# HuLaMachDieuKhienSCH.net
KiCad netlist of a schematic drawn in Altium Designer
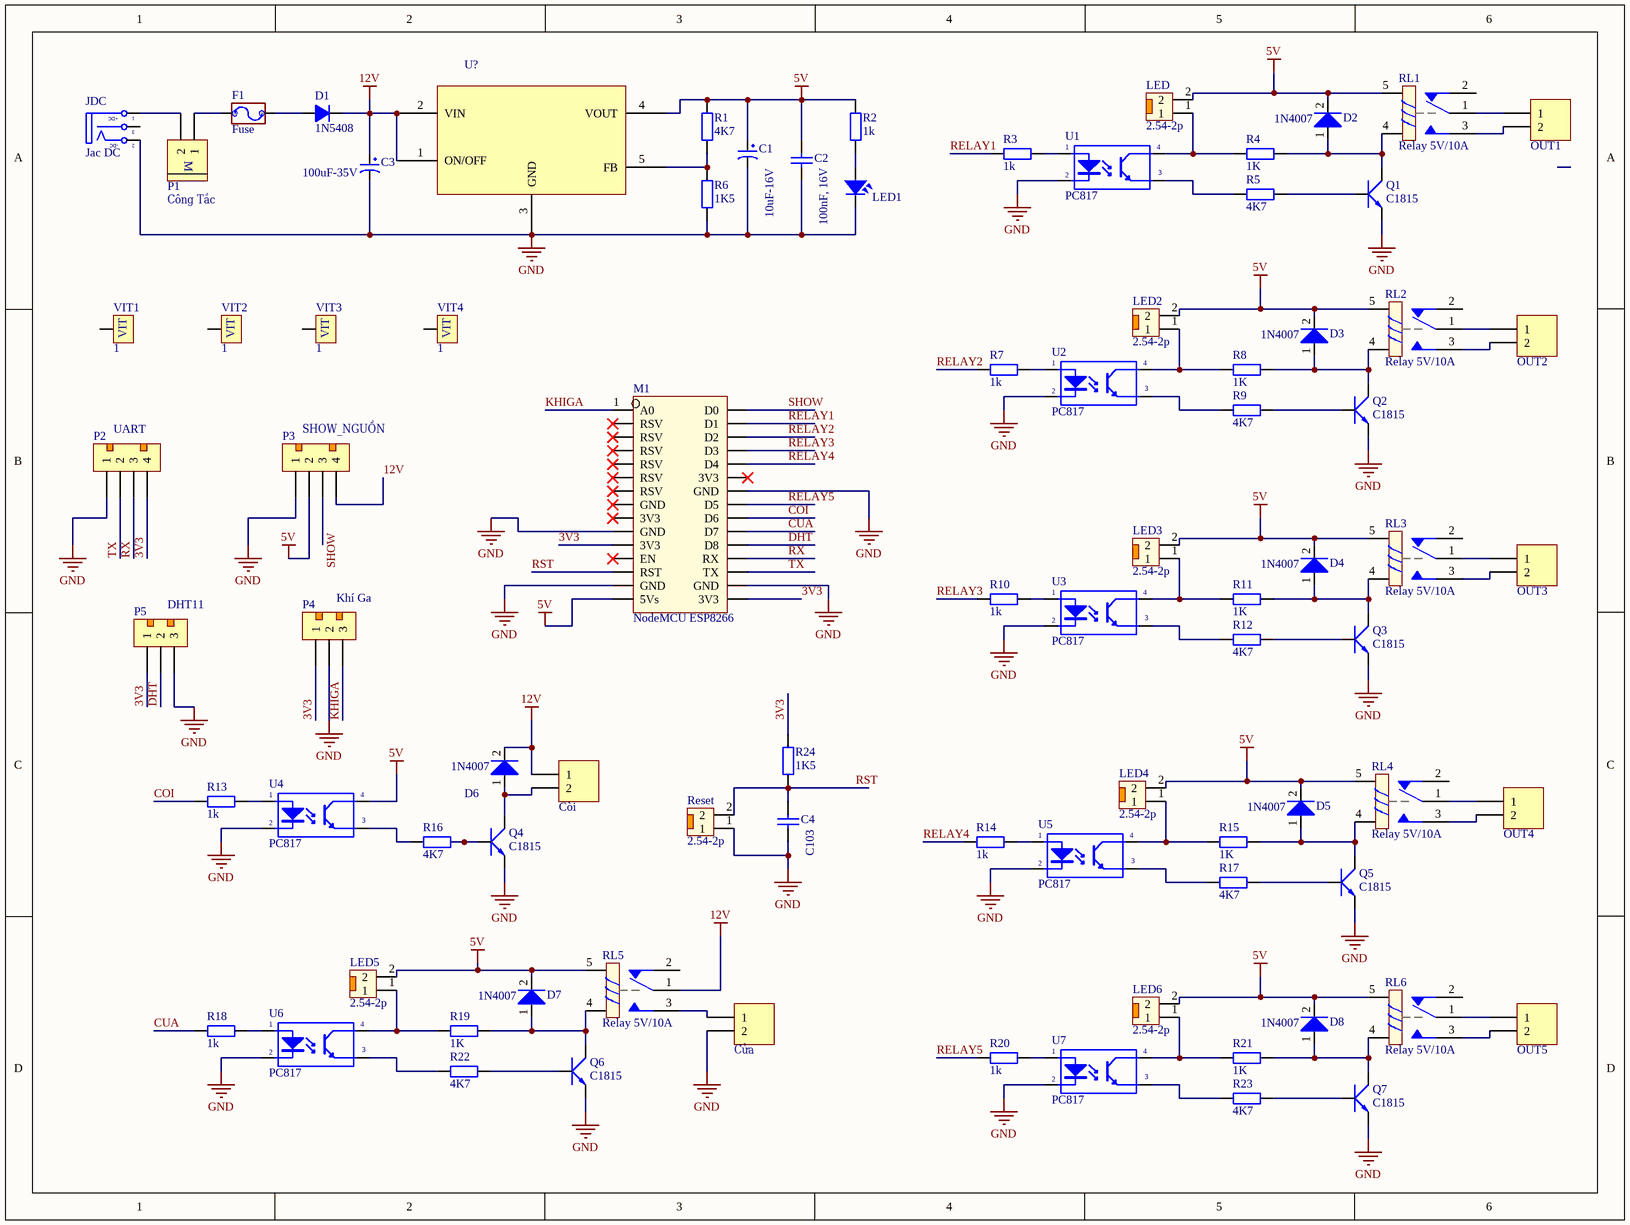
[diagram p0: HuLaMachDieuKhienSCH.SchDoc]

(export (version "E")
  (design (tool "Eeschema 10.0.6"))
  (components
    (comp (ref "C1")
      (value "10uF-16V")
      (footprint "tu hoa 4mm")
      (description "Cắm")
      (libsource (lib "SCH Chuan") (part "Tu Hoa 10uF 16V 4x7"))
    )
    (comp (ref "C2")
      (value "100nF, 16V")
      (footprint "CAPNTO2.54-3.05x1.78A")
      (description "CAP NPO CAPNTO 22pF 100V 10%")
      (fields (field (name "Comment") "5AK220KABAA"))
      (libsource (lib "NhomLib") (part "5AK220KABAA"))
    )
    (comp (ref "C3")
      (value "100uF-35V")
      (footprint "tu hoa 6.5mm")
      (description "Cắm")
      (libsource (lib "SCH Chuan") (part "Tu Hoa 100uF 35V 6x8"))
    )
    (comp (ref "C4")
      (value "C103")
      (footprint "CAPNTO2.54-3.05x1.78A")
      (description "CAP NPO CAPNTO 22pF 100V 10%")
      (fields (field (name "Comment") "5AK220KABAA"))
      (libsource (lib "NhomLib") (part "5AK220KABAA"))
    )
    (comp (ref "Còi")
      (value "Header 2_1")
      (footprint "HED2")
      (description "Header, 2-Pin")
      (fields (field (name "MANUFACTURER") "Generic Components"))
      (libsource (lib "syhaunguyen") (part "Header 2_1"))
    )
    (comp (ref "Cửa")
      (value "Header 2_1")
      (footprint "HED2")
      (description "Header, 2-Pin")
      (fields (field (name "MANUFACTURER") "Generic Components"))
      (libsource (lib "syhaunguyen") (part "Header 2_1"))
    )
    (comp (ref "D1")
      (value "1N5408")
      (footprint "D5A")
      (description "Diode 5A")
      (libsource (lib "syhaunguyen") (part "D5A"))
    )
    (comp (ref "D2")
      (value "1N4007")
      (footprint "1N4007")
      (description "Diode LS 1A 1000V DO-41")
      (libsource (lib "LPSON") (part "1N4007"))
    )
    (comp (ref "D3")
      (value "1N4007")
      (footprint "1N4007")
      (description "Diode LS 1A 1000V DO-41")
      (libsource (lib "LPSON") (part "1N4007"))
    )
    (comp (ref "D4")
      (value "1N4007")
      (footprint "1N4007")
      (description "Diode LS 1A 1000V DO-41")
      (libsource (lib "LPSON") (part "1N4007"))
    )
    (comp (ref "D5")
      (value "1N4007")
      (footprint "1N4007")
      (description "Diode LS 1A 1000V DO-41")
      (libsource (lib "LPSON") (part "1N4007"))
    )
    (comp (ref "D6")
      (value "1N4007")
      (footprint "1N4007")
      (description "Diode LS 1A 1000V DO-41")
      (libsource (lib "LPSON") (part "1N4007"))
    )
    (comp (ref "D7")
      (value "1N4007")
      (footprint "1N4007")
      (description "Diode LS 1A 1000V DO-41")
      (libsource (lib "LPSON") (part "1N4007"))
    )
    (comp (ref "D8")
      (value "1N4007")
      (footprint "1N4007")
      (description "Diode LS 1A 1000V DO-41")
      (libsource (lib "LPSON") (part "1N4007"))
    )
    (comp (ref "F1") (value "Fuse") (footprint "FUSE_BOX") (libsource (lib "VPMyLibrary") (part "Fuse")))
    (comp (ref "JDC")
      (value "Jac DC")
      (footprint "DC-IN")
      (description "Jac DC input")
      (libsource (lib "LPSON") (part "DCIN"))
    )
    (comp (ref "LED")
      (value "2.54-2p")
      (footprint "Header Duc Thang 2P 2.54")
      (description "Cắm")
      (libsource (lib "NhomLib") (part "Header 2.54-2p Duc Thang"))
    )
    (comp (ref "LED1")
      (value "LED")
      (footprint "LED-3")
      (description "LED Single colour Green and Red")
      (libsource (lib "syhaunguyen") (part "LED"))
    )
    (comp (ref "LED2")
      (value "2.54-2p")
      (footprint "Header Duc Thang 2P 2.54")
      (description "Cắm")
      (libsource (lib "NhomLib") (part "Header 2.54-2p Duc Thang"))
    )
    (comp (ref "LED3")
      (value "2.54-2p")
      (footprint "Header Duc Thang 2P 2.54")
      (description "Cắm")
      (libsource (lib "NhomLib") (part "Header 2.54-2p Duc Thang"))
    )
    (comp (ref "LED4")
      (value "2.54-2p")
      (footprint "Header Duc Thang 2P 2.54")
      (description "Cắm")
      (libsource (lib "NhomLib") (part "Header 2.54-2p Duc Thang"))
    )
    (comp (ref "LED5")
      (value "2.54-2p")
      (footprint "Header Duc Thang 2P 2.54")
      (description "Cắm")
      (libsource (lib "NhomLib") (part "Header 2.54-2p Duc Thang"))
    )
    (comp (ref "LED6")
      (value "2.54-2p")
      (footprint "Header Duc Thang 2P 2.54")
      (description "Cắm")
      (libsource (lib "NhomLib") (part "Header 2.54-2p Duc Thang"))
    )
    (comp (ref "M1")
      (value "NodeMCU ESP8266")
      (footprint "NodeMCU ESP8266")
      (libsource (lib "NodeMCU ESP8266") (part "NodeMCU ESP8266"))
    )
    (comp (ref "MIC1")
      (value "U?")
      (footprint "Mic5V")
      (description "3A")
      (libsource (lib "node_mcu") (part "Mic5V"))
    )
    (comp (ref "OUT1")
      (value "Header 2_1")
      (footprint "HED2")
      (description "Header, 2-Pin")
      (fields (field (name "MANUFACTURER") "Generic Components"))
      (libsource (lib "syhaunguyen") (part "Header 2_1"))
    )
    (comp (ref "OUT2")
      (value "Header 2_1")
      (footprint "HED2")
      (description "Header, 2-Pin")
      (fields (field (name "MANUFACTURER") "Generic Components"))
      (libsource (lib "syhaunguyen") (part "Header 2_1"))
    )
    (comp (ref "OUT3")
      (value "Header 2_1")
      (footprint "HED2")
      (description "Header, 2-Pin")
      (fields (field (name "MANUFACTURER") "Generic Components"))
      (libsource (lib "syhaunguyen") (part "Header 2_1"))
    )
    (comp (ref "OUT4")
      (value "Header 2_1")
      (footprint "HED2")
      (description "Header, 2-Pin")
      (fields (field (name "MANUFACTURER") "Generic Components"))
      (libsource (lib "syhaunguyen") (part "Header 2_1"))
    )
    (comp (ref "OUT5")
      (value "Header 2_1")
      (footprint "HED2")
      (description "Header, 2-Pin")
      (fields (field (name "MANUFACTURER") "Generic Components"))
      (libsource (lib "syhaunguyen") (part "Header 2_1"))
    )
    (comp (ref "P1")
      (value "Công Tắc")
      (footprint "Medium - Header 2")
      (description "Header, 2-Pin, Medium")
      (fields (field (name "PUBLISHER") "Altium Limited"))
      (libsource (lib "BYTECH_HW_LIB_2019") (part "Header 2 - M"))
    )
    (comp (ref "P2")
      (value "UART")
      (footprint "Header Duc Thang 4p 2.54")
      (description "Cắm")
      (libsource (lib "NhomLib") (part "Header 2.54_4p Duc Thang"))
    )
    (comp (ref "P3")
      (value "SHOW_NGUỒN")
      (footprint "Header Duc Thang 4p 2.54")
      (description "Cắm")
      (libsource (lib "NhomLib") (part "Header 2.54_4p Duc Thang"))
    )
    (comp (ref "P4")
      (value "Khí Ga")
      (footprint "Header duc thang 3p 2.54")
      (description "Cắm")
      (libsource (lib "SCH Chuan") (part "Header 2.54_3p Duc Thang"))
    )
    (comp (ref "P5")
      (value "DHT11")
      (footprint "Header duc thang 3p 2.54")
      (description "Cắm")
      (libsource (lib "SCH Chuan") (part "Header 2.54_3p Duc Thang"))
    )
    (comp (ref "Q1")
      (value "C1815")
      (footprint "QTO-92")
      (description "NPN 600mW, ECB")
      (libsource (lib "syhaunguyen") (part "C1815"))
    )
    (comp (ref "Q2")
      (value "C1815")
      (footprint "QTO-92")
      (description "NPN 600mW, ECB")
      (libsource (lib "syhaunguyen") (part "C1815"))
    )
    (comp (ref "Q3")
      (value "C1815")
      (footprint "QTO-92")
      (description "NPN 600mW, ECB")
      (libsource (lib "syhaunguyen") (part "C1815"))
    )
    (comp (ref "Q4")
      (value "C1815")
      (footprint "QTO-92")
      (description "NPN 600mW, ECB")
      (libsource (lib "syhaunguyen") (part "C1815"))
    )
    (comp (ref "Q5")
      (value "C1815")
      (footprint "QTO-92")
      (description "NPN 600mW, ECB")
      (libsource (lib "syhaunguyen") (part "C1815"))
    )
    (comp (ref "Q6")
      (value "C1815")
      (footprint "QTO-92")
      (description "NPN 600mW, ECB")
      (libsource (lib "syhaunguyen") (part "C1815"))
    )
    (comp (ref "Q7")
      (value "C1815")
      (footprint "QTO-92")
      (description "NPN 600mW, ECB")
      (libsource (lib "syhaunguyen") (part "C1815"))
    )
    (comp (ref "R1")
      (value "4K7")
      (footprint "R1/4W")
      (description "Resistor 1/4W")
      (libsource (lib "syhaunguyen") (part "R1/4W"))
    )
    (comp (ref "R2")
      (value "1k")
      (footprint "R1/4W")
      (description "Resistor 1/4W")
      (libsource (lib "syhaunguyen") (part "R1/4W"))
    )
    (comp (ref "R3")
      (value "1k")
      (footprint "R1/4W")
      (description "Resistor 1/4W")
      (libsource (lib "syhaunguyen") (part "R1/4W"))
    )
    (comp (ref "R4")
      (value "1K")
      (footprint "R1/4W")
      (description "Resistor 1/4W")
      (libsource (lib "syhaunguyen") (part "R1/4W"))
    )
    (comp (ref "R5")
      (value "4K7")
      (footprint "R1/4W")
      (description "Resistor 1/4W")
      (libsource (lib "syhaunguyen") (part "R1/4W"))
    )
    (comp (ref "R6")
      (value "1K5")
      (footprint "R1/4W")
      (description "Resistor 1/4W")
      (libsource (lib "syhaunguyen") (part "R1/4W"))
    )
    (comp (ref "R7")
      (value "1k")
      (footprint "R1/4W")
      (description "Resistor 1/4W")
      (libsource (lib "syhaunguyen") (part "R1/4W"))
    )
    (comp (ref "R8")
      (value "1K")
      (footprint "R1/4W")
      (description "Resistor 1/4W")
      (libsource (lib "syhaunguyen") (part "R1/4W"))
    )
    (comp (ref "R9")
      (value "4K7")
      (footprint "R1/4W")
      (description "Resistor 1/4W")
      (libsource (lib "syhaunguyen") (part "R1/4W"))
    )
    (comp (ref "R10")
      (value "1k")
      (footprint "R1/4W")
      (description "Resistor 1/4W")
      (libsource (lib "syhaunguyen") (part "R1/4W"))
    )
    (comp (ref "R11")
      (value "1K")
      (footprint "R1/4W")
      (description "Resistor 1/4W")
      (libsource (lib "syhaunguyen") (part "R1/4W"))
    )
    (comp (ref "R12")
      (value "4K7")
      (footprint "R1/4W")
      (description "Resistor 1/4W")
      (libsource (lib "syhaunguyen") (part "R1/4W"))
    )
    (comp (ref "R13")
      (value "1k")
      (footprint "R1/4W")
      (description "Resistor 1/4W")
      (libsource (lib "syhaunguyen") (part "R1/4W"))
    )
    (comp (ref "R14")
      (value "1k")
      (footprint "R1/4W")
      (description "Resistor 1/4W")
      (libsource (lib "syhaunguyen") (part "R1/4W"))
    )
    (comp (ref "R15")
      (value "1K")
      (footprint "R1/4W")
      (description "Resistor 1/4W")
      (libsource (lib "syhaunguyen") (part "R1/4W"))
    )
    (comp (ref "R16")
      (value "4K7")
      (footprint "R1/4W")
      (description "Resistor 1/4W")
      (libsource (lib "syhaunguyen") (part "R1/4W"))
    )
    (comp (ref "R17")
      (value "4K7")
      (footprint "R1/4W")
      (description "Resistor 1/4W")
      (libsource (lib "syhaunguyen") (part "R1/4W"))
    )
    (comp (ref "R18")
      (value "1k")
      (footprint "R1/4W")
      (description "Resistor 1/4W")
      (libsource (lib "syhaunguyen") (part "R1/4W"))
    )
    (comp (ref "R19")
      (value "1K")
      (footprint "R1/4W")
      (description "Resistor 1/4W")
      (libsource (lib "syhaunguyen") (part "R1/4W"))
    )
    (comp (ref "R20")
      (value "1k")
      (footprint "R1/4W")
      (description "Resistor 1/4W")
      (libsource (lib "syhaunguyen") (part "R1/4W"))
    )
    (comp (ref "R21")
      (value "1K")
      (footprint "R1/4W")
      (description "Resistor 1/4W")
      (libsource (lib "syhaunguyen") (part "R1/4W"))
    )
    (comp (ref "R22")
      (value "4K7")
      (footprint "R1/4W")
      (description "Resistor 1/4W")
      (libsource (lib "syhaunguyen") (part "R1/4W"))
    )
    (comp (ref "R23")
      (value "4K7")
      (footprint "R1/4W")
      (description "Resistor 1/4W")
      (libsource (lib "syhaunguyen") (part "R1/4W"))
    )
    (comp (ref "R24")
      (value "1K5")
      (footprint "R1/4W")
      (description "Resistor 1/4W")
      (libsource (lib "syhaunguyen") (part "R1/4W"))
    )
    (comp (ref "Reset")
      (value "2.54-2p")
      (footprint "Header Duc Thang 2P 2.54")
      (description "Cắm")
      (libsource (lib "NhomLib") (part "Header 2.54-2p Duc Thang"))
    )
    (comp (ref "RL1")
      (value "Relay 5V/10A")
      (footprint "RL_10A_5V")
      (description "Relay SPDT,10A - 12VDC 5 Pin")
      (libsource (lib "LPSON") (part "Relay 5V10A"))
    )
    (comp (ref "RL2")
      (value "Relay 5V/10A")
      (footprint "RL_10A_5V")
      (description "Relay SPDT,10A - 12VDC 5 Pin")
      (libsource (lib "LPSON") (part "Relay 5V10A"))
    )
    (comp (ref "RL3")
      (value "Relay 5V/10A")
      (footprint "RL_10A_5V")
      (description "Relay SPDT,10A - 12VDC 5 Pin")
      (libsource (lib "LPSON") (part "Relay 5V10A"))
    )
    (comp (ref "RL4")
      (value "Relay 5V/10A")
      (footprint "RL_10A_5V")
      (description "Relay SPDT,10A - 12VDC 5 Pin")
      (libsource (lib "LPSON") (part "Relay 5V10A"))
    )
    (comp (ref "RL5")
      (value "Relay 5V/10A")
      (footprint "RL_10A_5V")
      (description "Relay SPDT,10A - 12VDC 5 Pin")
      (libsource (lib "LPSON") (part "Relay 5V10A"))
    )
    (comp (ref "RL6")
      (value "Relay 5V/10A")
      (footprint "RL_10A_5V")
      (description "Relay SPDT,10A - 12VDC 5 Pin")
      (libsource (lib "LPSON") (part "Relay 5V10A"))
    )
    (comp (ref "U1")
      (value "PC817")
      (footprint "DIP4/W0.3")
      (description "Single Opto")
      (libsource (lib "syhaunguyen") (part "PC817"))
    )
    (comp (ref "U2")
      (value "PC817")
      (footprint "DIP4/W0.3")
      (description "Single Opto")
      (libsource (lib "syhaunguyen") (part "PC817"))
    )
    (comp (ref "U3")
      (value "PC817")
      (footprint "DIP4/W0.3")
      (description "Single Opto")
      (libsource (lib "syhaunguyen") (part "PC817"))
    )
    (comp (ref "U4")
      (value "PC817")
      (footprint "DIP4/W0.3")
      (description "Single Opto")
      (libsource (lib "syhaunguyen") (part "PC817"))
    )
    (comp (ref "U5")
      (value "PC817")
      (footprint "DIP4/W0.3")
      (description "Single Opto")
      (libsource (lib "syhaunguyen") (part "PC817"))
    )
    (comp (ref "U6")
      (value "PC817")
      (footprint "DIP4/W0.3")
      (description "Single Opto")
      (libsource (lib "syhaunguyen") (part "PC817"))
    )
    (comp (ref "U7")
      (value "PC817")
      (footprint "DIP4/W0.3")
      (description "Single Opto")
      (libsource (lib "syhaunguyen") (part "PC817"))
    )
    (comp (ref "VIT1")
      (value "1")
      (footprint "VIT")
      (description "Oc Vit")
      (libsource (lib "NhomLib") (part "VIT"))
    )
    (comp (ref "VIT2")
      (value "1")
      (footprint "VIT")
      (description "Oc Vit")
      (libsource (lib "NhomLib") (part "VIT"))
    )
    (comp (ref "VIT3")
      (value "1")
      (footprint "VIT")
      (description "Oc Vit")
      (libsource (lib "NhomLib") (part "VIT"))
    )
    (comp (ref "VIT4")
      (value "1")
      (footprint "VIT")
      (description "Oc Vit")
      (libsource (lib "NhomLib") (part "VIT"))
    )
  )
  (nets
    (net (code "1") (name "/3V3") (class "Default")
      (node (ref "M1") (pin "11") (pinfunction "3V3_11") (pintype "passive"))
      (node (ref "M1") (pin "16") (pinfunction "3V3_16") (pintype "passive"))
      (node (ref "P2") (pin "4") (pinfunction "4_4") (pintype "passive"))
      (node (ref "P4") (pin "1") (pinfunction "1_1") (pintype "passive"))
      (node (ref "P5") (pin "1") (pinfunction "1_1") (pintype "passive"))
      (node (ref "R24") (pin "2") (pinfunction "2_2") (pintype "passive"))
    )
    (net (code "2") (name "/COI") (class "Default")
      (node (ref "M1") (pin "22") (pinfunction "D6_22") (pintype "passive"))
      (node (ref "R13") (pin "1") (pinfunction "1_1") (pintype "passive"))
    )
    (net (code "3") (name "/CUA") (class "Default")
      (node (ref "M1") (pin "21") (pinfunction "D7_21") (pintype "passive"))
      (node (ref "R18") (pin "1") (pinfunction "1_1") (pintype "passive"))
    )
    (net (code "4") (name "/DHT") (class "Default")
      (node (ref "M1") (pin "20") (pinfunction "D8_20") (pintype "passive"))
      (node (ref "P5") (pin "2") (pinfunction "2_2") (pintype "passive"))
    )
    (net (code "5") (name "/KHIGA") (class "Default")
      (node (ref "M1") (pin "1") (pinfunction "A0_1") (pintype "passive"))
      (node (ref "P4") (pin "3") (pinfunction "3_3") (pintype "passive"))
    )
    (net (code "6") (name "/RELAY1") (class "Default")
      (node (ref "M1") (pin "29") (pinfunction "D1_29") (pintype "passive"))
      (node (ref "R3") (pin "1") (pinfunction "1_1") (pintype "passive"))
    )
    (net (code "7") (name "/RELAY2") (class "Default")
      (node (ref "M1") (pin "28") (pinfunction "D2_28") (pintype "passive"))
      (node (ref "R7") (pin "1") (pinfunction "1_1") (pintype "passive"))
    )
    (net (code "8") (name "/RELAY3") (class "Default")
      (node (ref "M1") (pin "27") (pinfunction "D3_27") (pintype "passive"))
      (node (ref "R10") (pin "1") (pinfunction "1_1") (pintype "passive"))
    )
    (net (code "9") (name "/RELAY4") (class "Default")
      (node (ref "M1") (pin "26") (pinfunction "D4_26") (pintype "passive"))
      (node (ref "R14") (pin "1") (pinfunction "1_1") (pintype "passive"))
    )
    (net (code "10") (name "/RELAY5") (class "Default")
      (node (ref "M1") (pin "23") (pinfunction "D5_23") (pintype "passive"))
      (node (ref "R20") (pin "1") (pinfunction "1_1") (pintype "passive"))
    )
    (net (code "11") (name "/RST") (class "Default")
      (node (ref "C4") (pin "1") (pinfunction "1_1") (pintype "passive"))
      (node (ref "M1") (pin "13") (pinfunction "RST_13") (pintype "passive"))
      (node (ref "R24") (pin "1") (pinfunction "1_1") (pintype "passive"))
      (node (ref "Reset") (pin "2") (pinfunction "2_2") (pintype "passive"))
    )
    (net (code "12") (name "/RX") (class "Default")
      (node (ref "M1") (pin "19") (pinfunction "RX_19") (pintype "passive"))
      (node (ref "P2") (pin "3") (pinfunction "3_3") (pintype "passive"))
    )
    (net (code "13") (name "/SHOW") (class "Default")
      (node (ref "M1") (pin "30") (pinfunction "D0_30") (pintype "passive"))
      (node (ref "P3") (pin "3") (pinfunction "3_3") (pintype "passive"))
    )
    (net (code "14") (name "/TX") (class "Default")
      (node (ref "M1") (pin "18") (pinfunction "TX_18") (pintype "passive"))
      (node (ref "P2") (pin "2") (pinfunction "2_2") (pintype "passive"))
    )
    (net (code "15") (name "5V") (class "Default")
      (node (ref "C1") (pin "1") (pinfunction "1_1") (pintype "passive"))
      (node (ref "C2") (pin "1") (pinfunction "1_1") (pintype "passive"))
      (node (ref "D2") (pin "2") (pinfunction "K_2") (pintype "passive"))
      (node (ref "D3") (pin "2") (pinfunction "K_2") (pintype "passive"))
      (node (ref "D4") (pin "2") (pinfunction "K_2") (pintype "passive"))
      (node (ref "D5") (pin "2") (pinfunction "K_2") (pintype "passive"))
      (node (ref "D7") (pin "2") (pinfunction "K_2") (pintype "passive"))
      (node (ref "D8") (pin "2") (pinfunction "K_2") (pintype "passive"))
      (node (ref "LED") (pin "2") (pinfunction "2_2") (pintype "passive"))
      (node (ref "LED2") (pin "2") (pinfunction "2_2") (pintype "passive"))
      (node (ref "LED3") (pin "2") (pinfunction "2_2") (pintype "passive"))
      (node (ref "LED4") (pin "2") (pinfunction "2_2") (pintype "passive"))
      (node (ref "LED5") (pin "2") (pinfunction "2_2") (pintype "passive"))
      (node (ref "LED6") (pin "2") (pinfunction "2_2") (pintype "passive"))
      (node (ref "M1") (pin "15") (pinfunction "5Vs_15") (pintype "passive"))
      (node (ref "MIC1") (pin "4") (pinfunction "VOUT_4") (pintype "passive"))
      (node (ref "P3") (pin "2") (pinfunction "2_2") (pintype "passive"))
      (node (ref "R1") (pin "2") (pinfunction "2_2") (pintype "passive"))
      (node (ref "R2") (pin "2") (pinfunction "2_2") (pintype "passive"))
      (node (ref "RL1") (pin "5") (pinfunction "5_5") (pintype "passive"))
      (node (ref "RL2") (pin "5") (pinfunction "5_5") (pintype "passive"))
      (node (ref "RL3") (pin "5") (pinfunction "5_5") (pintype "passive"))
      (node (ref "RL4") (pin "5") (pinfunction "5_5") (pintype "passive"))
      (node (ref "RL5") (pin "5") (pinfunction "5_5") (pintype "passive"))
      (node (ref "RL6") (pin "5") (pinfunction "5_5") (pintype "passive"))
      (node (ref "U4") (pin "4") (pinfunction "C_4") (pintype "passive"))
    )
    (net (code "16") (name "12V") (class "Default")
      (node (ref "C3") (pin "1") (pinfunction "1_1") (pintype "passive"))
      (node (ref "Còi") (pin "1") (pinfunction "1_1") (pintype "passive"))
      (node (ref "D1") (pin "2") (pinfunction "K_2") (pintype "passive"))
      (node (ref "D6") (pin "2") (pinfunction "K_2") (pintype "passive"))
      (node (ref "MIC1") (pin "1") (pinfunction "ON/OFF_1") (pintype "passive"))
      (node (ref "MIC1") (pin "2") (pinfunction "VIN_2") (pintype "passive"))
      (node (ref "P3") (pin "4") (pinfunction "4_4") (pintype "passive"))
      (node (ref "RL5") (pin "1") (pinfunction "1_1") (pintype "passive"))
    )
    (net (code "17") (name "GND") (class "Default")
      (node (ref "C1") (pin "2") (pinfunction "2_2") (pintype "passive"))
      (node (ref "C2") (pin "2") (pinfunction "2_2") (pintype "passive"))
      (node (ref "C3") (pin "2") (pinfunction "2_2") (pintype "passive"))
      (node (ref "C4") (pin "2") (pinfunction "2_2") (pintype "passive"))
      (node (ref "Cửa") (pin "2") (pinfunction "2_2") (pintype "passive"))
      (node (ref "JDC") (pin "2") (pinfunction "TN_2") (pintype "passive"))
      (node (ref "LED1") (pin "2") (pinfunction "2_2") (pintype "passive"))
      (node (ref "M1") (pin "10") (pinfunction "GND_10") (pintype "passive"))
      (node (ref "M1") (pin "14") (pinfunction "GND_14") (pintype "passive"))
      (node (ref "M1") (pin "17") (pinfunction "GND_17") (pintype "passive"))
      (node (ref "M1") (pin "24") (pinfunction "GND_24") (pintype "passive"))
      (node (ref "MIC1") (pin "3") (pinfunction "GND_3") (pintype "passive"))
      (node (ref "P2") (pin "1") (pinfunction "1_1") (pintype "passive"))
      (node (ref "P3") (pin "1") (pinfunction "1_1") (pintype "passive"))
      (node (ref "P4") (pin "2") (pinfunction "2_2") (pintype "passive"))
      (node (ref "P5") (pin "3") (pinfunction "3_3") (pintype "passive"))
      (node (ref "Q1") (pin "1") (pinfunction "E_1") (pintype "passive"))
      (node (ref "Q2") (pin "1") (pinfunction "E_1") (pintype "passive"))
      (node (ref "Q3") (pin "1") (pinfunction "E_1") (pintype "passive"))
      (node (ref "Q4") (pin "1") (pinfunction "E_1") (pintype "passive"))
      (node (ref "Q5") (pin "1") (pinfunction "E_1") (pintype "passive"))
      (node (ref "Q6") (pin "1") (pinfunction "E_1") (pintype "passive"))
      (node (ref "Q7") (pin "1") (pinfunction "E_1") (pintype "passive"))
      (node (ref "R6") (pin "1") (pinfunction "1_1") (pintype "passive"))
      (node (ref "Reset") (pin "1") (pinfunction "1_1") (pintype "passive"))
      (node (ref "U1") (pin "2") (pinfunction "K_2") (pintype "passive"))
      (node (ref "U2") (pin "2") (pinfunction "K_2") (pintype "passive"))
      (node (ref "U3") (pin "2") (pinfunction "K_2") (pintype "passive"))
      (node (ref "U4") (pin "2") (pinfunction "K_2") (pintype "passive"))
      (node (ref "U5") (pin "2") (pinfunction "K_2") (pintype "passive"))
      (node (ref "U6") (pin "2") (pinfunction "K_2") (pintype "passive"))
      (node (ref "U7") (pin "2") (pinfunction "K_2") (pintype "passive"))
    )
    (net (code "18") (name "Net-(Cửa-Pad1)") (class "Default")
      (node (ref "Cửa") (pin "1") (pinfunction "1_1") (pintype "passive"))
      (node (ref "RL5") (pin "3") (pinfunction "3_3") (pintype "passive"))
    )
    (net (code "19") (name "Net-(D1-A)") (class "Default")
      (node (ref "D1") (pin "1") (pinfunction "A_1") (pintype "passive"))
      (node (ref "F1") (pin "2") (pinfunction "2_2") (pintype "passive"))
    )
    (net (code "20") (name "Net-(D2-A)") (class "Default")
      (node (ref "D2") (pin "1") (pinfunction "A_1") (pintype "passive"))
      (node (ref "Q1") (pin "2") (pinfunction "C_2") (pintype "passive"))
      (node (ref "R4") (pin "2") (pinfunction "2_2") (pintype "passive"))
      (node (ref "RL1") (pin "4") (pinfunction "4_4") (pintype "passive"))
    )
    (net (code "21") (name "Net-(D3-A)") (class "Default")
      (node (ref "D3") (pin "1") (pinfunction "A_1") (pintype "passive"))
      (node (ref "Q2") (pin "2") (pinfunction "C_2") (pintype "passive"))
      (node (ref "R8") (pin "2") (pinfunction "2_2") (pintype "passive"))
      (node (ref "RL2") (pin "4") (pinfunction "4_4") (pintype "passive"))
    )
    (net (code "22") (name "Net-(D4-A)") (class "Default")
      (node (ref "D4") (pin "1") (pinfunction "A_1") (pintype "passive"))
      (node (ref "Q3") (pin "2") (pinfunction "C_2") (pintype "passive"))
      (node (ref "R11") (pin "2") (pinfunction "2_2") (pintype "passive"))
      (node (ref "RL3") (pin "4") (pinfunction "4_4") (pintype "passive"))
    )
    (net (code "23") (name "Net-(D5-A)") (class "Default")
      (node (ref "D5") (pin "1") (pinfunction "A_1") (pintype "passive"))
      (node (ref "Q5") (pin "2") (pinfunction "C_2") (pintype "passive"))
      (node (ref "R15") (pin "2") (pinfunction "2_2") (pintype "passive"))
      (node (ref "RL4") (pin "4") (pinfunction "4_4") (pintype "passive"))
    )
    (net (code "24") (name "Net-(D6-A)") (class "Default")
      (node (ref "Còi") (pin "2") (pinfunction "2_2") (pintype "passive"))
      (node (ref "D6") (pin "1") (pinfunction "A_1") (pintype "passive"))
      (node (ref "Q4") (pin "2") (pinfunction "C_2") (pintype "passive"))
    )
    (net (code "25") (name "Net-(D7-A)") (class "Default")
      (node (ref "D7") (pin "1") (pinfunction "A_1") (pintype "passive"))
      (node (ref "Q6") (pin "2") (pinfunction "C_2") (pintype "passive"))
      (node (ref "R19") (pin "2") (pinfunction "2_2") (pintype "passive"))
      (node (ref "RL5") (pin "4") (pinfunction "4_4") (pintype "passive"))
    )
    (net (code "26") (name "Net-(D8-A)") (class "Default")
      (node (ref "D8") (pin "1") (pinfunction "A_1") (pintype "passive"))
      (node (ref "Q7") (pin "2") (pinfunction "C_2") (pintype "passive"))
      (node (ref "R21") (pin "2") (pinfunction "2_2") (pintype "passive"))
      (node (ref "RL6") (pin "4") (pinfunction "4_4") (pintype "passive"))
    )
    (net (code "27") (name "Net-(F1-Pad1)") (class "Default")
      (node (ref "F1") (pin "1") (pinfunction "1_1") (pintype "passive"))
      (node (ref "P1") (pin "1") (pinfunction "1_1") (pintype "passive"))
    )
    (net (code "28") (name "Net-(JDC-T)") (class "Default")
      (node (ref "JDC") (pin "1") (pinfunction "T_1") (pintype "passive"))
      (node (ref "P1") (pin "2") (pinfunction "2_2") (pintype "passive"))
    )
    (net (code "29") (name "Net-(LED1-Pad1)") (class "Default")
      (node (ref "LED1") (pin "1") (pinfunction "1_1") (pintype "passive"))
      (node (ref "R2") (pin "1") (pinfunction "1_1") (pintype "passive"))
    )
    (net (code "30") (name "Net-(MIC1-FB)") (class "Default")
      (node (ref "MIC1") (pin "5") (pinfunction "FB_5") (pintype "passive"))
      (node (ref "R1") (pin "1") (pinfunction "1_1") (pintype "passive"))
      (node (ref "R6") (pin "2") (pinfunction "2_2") (pintype "passive"))
    )
    (net (code "31") (name "Net-(OUT1-Pad1)") (class "Default")
      (node (ref "OUT1") (pin "1") (pinfunction "1_1") (pintype "passive"))
      (node (ref "RL1") (pin "1") (pinfunction "1_1") (pintype "passive"))
    )
    (net (code "32") (name "Net-(OUT1-Pad2)") (class "Default")
      (node (ref "OUT1") (pin "2") (pinfunction "2_2") (pintype "passive"))
      (node (ref "RL1") (pin "3") (pinfunction "3_3") (pintype "passive"))
    )
    (net (code "33") (name "Net-(OUT2-Pad1)") (class "Default")
      (node (ref "OUT2") (pin "1") (pinfunction "1_1") (pintype "passive"))
      (node (ref "RL2") (pin "1") (pinfunction "1_1") (pintype "passive"))
    )
    (net (code "34") (name "Net-(OUT2-Pad2)") (class "Default")
      (node (ref "OUT2") (pin "2") (pinfunction "2_2") (pintype "passive"))
      (node (ref "RL2") (pin "3") (pinfunction "3_3") (pintype "passive"))
    )
    (net (code "35") (name "Net-(OUT3-Pad1)") (class "Default")
      (node (ref "OUT3") (pin "1") (pinfunction "1_1") (pintype "passive"))
      (node (ref "RL3") (pin "1") (pinfunction "1_1") (pintype "passive"))
    )
    (net (code "36") (name "Net-(OUT3-Pad2)") (class "Default")
      (node (ref "OUT3") (pin "2") (pinfunction "2_2") (pintype "passive"))
      (node (ref "RL3") (pin "3") (pinfunction "3_3") (pintype "passive"))
    )
    (net (code "37") (name "Net-(OUT4-Pad1)") (class "Default")
      (node (ref "OUT4") (pin "1") (pinfunction "1_1") (pintype "passive"))
      (node (ref "RL4") (pin "1") (pinfunction "1_1") (pintype "passive"))
    )
    (net (code "38") (name "Net-(OUT4-Pad2)") (class "Default")
      (node (ref "OUT4") (pin "2") (pinfunction "2_2") (pintype "passive"))
      (node (ref "RL4") (pin "3") (pinfunction "3_3") (pintype "passive"))
    )
    (net (code "39") (name "Net-(OUT5-Pad1)") (class "Default")
      (node (ref "OUT5") (pin "1") (pinfunction "1_1") (pintype "passive"))
      (node (ref "RL6") (pin "1") (pinfunction "1_1") (pintype "passive"))
    )
    (net (code "40") (name "Net-(OUT5-Pad2)") (class "Default")
      (node (ref "OUT5") (pin "2") (pinfunction "2_2") (pintype "passive"))
      (node (ref "RL6") (pin "3") (pinfunction "3_3") (pintype "passive"))
    )
    (net (code "41") (name "Net-(Q1-B)") (class "Default")
      (node (ref "Q1") (pin "3") (pinfunction "B_3") (pintype "passive"))
      (node (ref "R5") (pin "2") (pinfunction "2_2") (pintype "passive"))
    )
    (net (code "42") (name "Net-(Q2-B)") (class "Default")
      (node (ref "Q2") (pin "3") (pinfunction "B_3") (pintype "passive"))
      (node (ref "R9") (pin "2") (pinfunction "2_2") (pintype "passive"))
    )
    (net (code "43") (name "Net-(Q3-B)") (class "Default")
      (node (ref "Q3") (pin "3") (pinfunction "B_3") (pintype "passive"))
      (node (ref "R12") (pin "2") (pinfunction "2_2") (pintype "passive"))
    )
    (net (code "44") (name "Net-(Q4-B)") (class "Default")
      (node (ref "Q4") (pin "3") (pinfunction "B_3") (pintype "passive"))
      (node (ref "R16") (pin "2") (pinfunction "2_2") (pintype "passive"))
    )
    (net (code "45") (name "Net-(Q5-B)") (class "Default")
      (node (ref "Q5") (pin "3") (pinfunction "B_3") (pintype "passive"))
      (node (ref "R17") (pin "2") (pinfunction "2_2") (pintype "passive"))
    )
    (net (code "46") (name "Net-(Q6-B)") (class "Default")
      (node (ref "Q6") (pin "3") (pinfunction "B_3") (pintype "passive"))
      (node (ref "R22") (pin "2") (pinfunction "2_2") (pintype "passive"))
    )
    (net (code "47") (name "Net-(Q7-B)") (class "Default")
      (node (ref "Q7") (pin "3") (pinfunction "B_3") (pintype "passive"))
      (node (ref "R23") (pin "2") (pinfunction "2_2") (pintype "passive"))
    )
    (net (code "48") (name "Net-(U1-A)") (class "Default")
      (node (ref "R3") (pin "2") (pinfunction "2_2") (pintype "passive"))
      (node (ref "U1") (pin "1") (pinfunction "A_1") (pintype "passive"))
    )
    (net (code "49") (name "Net-(U1-C)") (class "Default")
      (node (ref "LED") (pin "1") (pinfunction "1_1") (pintype "passive"))
      (node (ref "R4") (pin "1") (pinfunction "1_1") (pintype "passive"))
      (node (ref "U1") (pin "4") (pinfunction "C_4") (pintype "passive"))
    )
    (net (code "50") (name "Net-(U1-E)") (class "Default")
      (node (ref "R5") (pin "1") (pinfunction "1_1") (pintype "passive"))
      (node (ref "U1") (pin "3") (pinfunction "E_3") (pintype "passive"))
    )
    (net (code "51") (name "Net-(U2-A)") (class "Default")
      (node (ref "R7") (pin "2") (pinfunction "2_2") (pintype "passive"))
      (node (ref "U2") (pin "1") (pinfunction "A_1") (pintype "passive"))
    )
    (net (code "52") (name "Net-(U2-C)") (class "Default")
      (node (ref "LED2") (pin "1") (pinfunction "1_1") (pintype "passive"))
      (node (ref "R8") (pin "1") (pinfunction "1_1") (pintype "passive"))
      (node (ref "U2") (pin "4") (pinfunction "C_4") (pintype "passive"))
    )
    (net (code "53") (name "Net-(U2-E)") (class "Default")
      (node (ref "R9") (pin "1") (pinfunction "1_1") (pintype "passive"))
      (node (ref "U2") (pin "3") (pinfunction "E_3") (pintype "passive"))
    )
    (net (code "54") (name "Net-(U3-A)") (class "Default")
      (node (ref "R10") (pin "2") (pinfunction "2_2") (pintype "passive"))
      (node (ref "U3") (pin "1") (pinfunction "A_1") (pintype "passive"))
    )
    (net (code "55") (name "Net-(U3-C)") (class "Default")
      (node (ref "LED3") (pin "1") (pinfunction "1_1") (pintype "passive"))
      (node (ref "R11") (pin "1") (pinfunction "1_1") (pintype "passive"))
      (node (ref "U3") (pin "4") (pinfunction "C_4") (pintype "passive"))
    )
    (net (code "56") (name "Net-(U3-E)") (class "Default")
      (node (ref "R12") (pin "1") (pinfunction "1_1") (pintype "passive"))
      (node (ref "U3") (pin "3") (pinfunction "E_3") (pintype "passive"))
    )
    (net (code "57") (name "Net-(U4-A)") (class "Default")
      (node (ref "R13") (pin "2") (pinfunction "2_2") (pintype "passive"))
      (node (ref "U4") (pin "1") (pinfunction "A_1") (pintype "passive"))
    )
    (net (code "58") (name "Net-(U4-E)") (class "Default")
      (node (ref "R16") (pin "1") (pinfunction "1_1") (pintype "passive"))
      (node (ref "U4") (pin "3") (pinfunction "E_3") (pintype "passive"))
    )
    (net (code "59") (name "Net-(U5-A)") (class "Default")
      (node (ref "R14") (pin "2") (pinfunction "2_2") (pintype "passive"))
      (node (ref "U5") (pin "1") (pinfunction "A_1") (pintype "passive"))
    )
    (net (code "60") (name "Net-(U5-C)") (class "Default")
      (node (ref "LED4") (pin "1") (pinfunction "1_1") (pintype "passive"))
      (node (ref "R15") (pin "1") (pinfunction "1_1") (pintype "passive"))
      (node (ref "U5") (pin "4") (pinfunction "C_4") (pintype "passive"))
    )
    (net (code "61") (name "Net-(U5-E)") (class "Default")
      (node (ref "R17") (pin "1") (pinfunction "1_1") (pintype "passive"))
      (node (ref "U5") (pin "3") (pinfunction "E_3") (pintype "passive"))
    )
    (net (code "62") (name "Net-(U6-A)") (class "Default")
      (node (ref "R18") (pin "2") (pinfunction "2_2") (pintype "passive"))
      (node (ref "U6") (pin "1") (pinfunction "A_1") (pintype "passive"))
    )
    (net (code "63") (name "Net-(U6-C)") (class "Default")
      (node (ref "LED5") (pin "1") (pinfunction "1_1") (pintype "passive"))
      (node (ref "R19") (pin "1") (pinfunction "1_1") (pintype "passive"))
      (node (ref "U6") (pin "4") (pinfunction "C_4") (pintype "passive"))
    )
    (net (code "64") (name "Net-(U6-E)") (class "Default")
      (node (ref "R22") (pin "1") (pinfunction "1_1") (pintype "passive"))
      (node (ref "U6") (pin "3") (pinfunction "E_3") (pintype "passive"))
    )
    (net (code "65") (name "Net-(U7-A)") (class "Default")
      (node (ref "R20") (pin "2") (pinfunction "2_2") (pintype "passive"))
      (node (ref "U7") (pin "1") (pinfunction "A_1") (pintype "passive"))
    )
    (net (code "66") (name "Net-(U7-C)") (class "Default")
      (node (ref "LED6") (pin "1") (pinfunction "1_1") (pintype "passive"))
      (node (ref "R21") (pin "1") (pinfunction "1_1") (pintype "passive"))
      (node (ref "U7") (pin "4") (pinfunction "C_4") (pintype "passive"))
    )
    (net (code "67") (name "Net-(U7-E)") (class "Default")
      (node (ref "R23") (pin "1") (pinfunction "1_1") (pintype "passive"))
      (node (ref "U7") (pin "3") (pinfunction "E_3") (pintype "passive"))
    )
    (net (code "68") (name "unconnected-(JDC-S-Pad3)") (class "Default")
      (node (ref "JDC") (pin "3") (pinfunction "S_3") (pintype "power_in"))
    )
    (net (code "69") (name "unconnected-(M1-3V3-Pad9)") (class "Default")
      (node (ref "M1") (pin "9") (pinfunction "3V3_9") (pintype "passive+no_connect"))
    )
    (net (code "70") (name "unconnected-(M1-3V3-Pad25)") (class "Default")
      (node (ref "M1") (pin "25") (pinfunction "3V3_25") (pintype "passive+no_connect"))
    )
    (net (code "71") (name "unconnected-(M1-EN-Pad12)") (class "Default")
      (node (ref "M1") (pin "12") (pinfunction "EN_12") (pintype "passive+no_connect"))
    )
    (net (code "72") (name "unconnected-(M1-GND-Pad8)") (class "Default")
      (node (ref "M1") (pin "8") (pinfunction "GND_8") (pintype "passive+no_connect"))
    )
    (net (code "73") (name "unconnected-(M1-RSV-Pad2)") (class "Default")
      (node (ref "M1") (pin "2") (pinfunction "RSV_2") (pintype "passive+no_connect"))
    )
    (net (code "74") (name "unconnected-(M1-RSV-Pad3)") (class "Default")
      (node (ref "M1") (pin "3") (pinfunction "RSV_3") (pintype "passive+no_connect"))
    )
    (net (code "75") (name "unconnected-(M1-RSV-Pad4)") (class "Default")
      (node (ref "M1") (pin "4") (pinfunction "RSV_4") (pintype "passive+no_connect"))
    )
    (net (code "76") (name "unconnected-(M1-RSV-Pad5)") (class "Default")
      (node (ref "M1") (pin "5") (pinfunction "RSV_5") (pintype "passive+no_connect"))
    )
    (net (code "77") (name "unconnected-(M1-RSV-Pad6)") (class "Default")
      (node (ref "M1") (pin "6") (pinfunction "RSV_6") (pintype "passive+no_connect"))
    )
    (net (code "78") (name "unconnected-(M1-RSV-Pad7)") (class "Default")
      (node (ref "M1") (pin "7") (pinfunction "RSV_7") (pintype "passive+no_connect"))
    )
    (net (code "79") (name "unconnected-(RL1-Pad2)") (class "Default")
      (node (ref "RL1") (pin "2") (pinfunction "2_2") (pintype "passive"))
    )
    (net (code "80") (name "unconnected-(RL2-Pad2)") (class "Default")
      (node (ref "RL2") (pin "2") (pinfunction "2_2") (pintype "passive"))
    )
    (net (code "81") (name "unconnected-(RL3-Pad2)") (class "Default")
      (node (ref "RL3") (pin "2") (pinfunction "2_2") (pintype "passive"))
    )
    (net (code "82") (name "unconnected-(RL4-Pad2)") (class "Default")
      (node (ref "RL4") (pin "2") (pinfunction "2_2") (pintype "passive"))
    )
    (net (code "83") (name "unconnected-(RL5-Pad2)") (class "Default")
      (node (ref "RL5") (pin "2") (pinfunction "2_2") (pintype "passive"))
    )
    (net (code "84") (name "unconnected-(RL6-Pad2)") (class "Default")
      (node (ref "RL6") (pin "2") (pinfunction "2_2") (pintype "passive"))
    )
    (net (code "85") (name "unconnected-(VIT1-1-PadVIT1)") (class "Default")
      (node (ref "VIT1") (pin "VIT1") (pinfunction "1_VIT1") (pintype "passive"))
    )
    (net (code "86") (name "unconnected-(VIT2-1-PadVIT1)") (class "Default")
      (node (ref "VIT2") (pin "VIT1") (pinfunction "1_VIT1") (pintype "passive"))
    )
    (net (code "87") (name "unconnected-(VIT3-1-PadVIT1)") (class "Default")
      (node (ref "VIT3") (pin "VIT1") (pinfunction "1_VIT1") (pintype "passive"))
    )
    (net (code "88") (name "unconnected-(VIT4-1-PadVIT1)") (class "Default")
      (node (ref "VIT4") (pin "VIT1") (pinfunction "1_VIT1") (pintype "passive"))
    )
  )
)
